# power_supply.net
KiCad netlist of a schematic drawn in Altium Designer
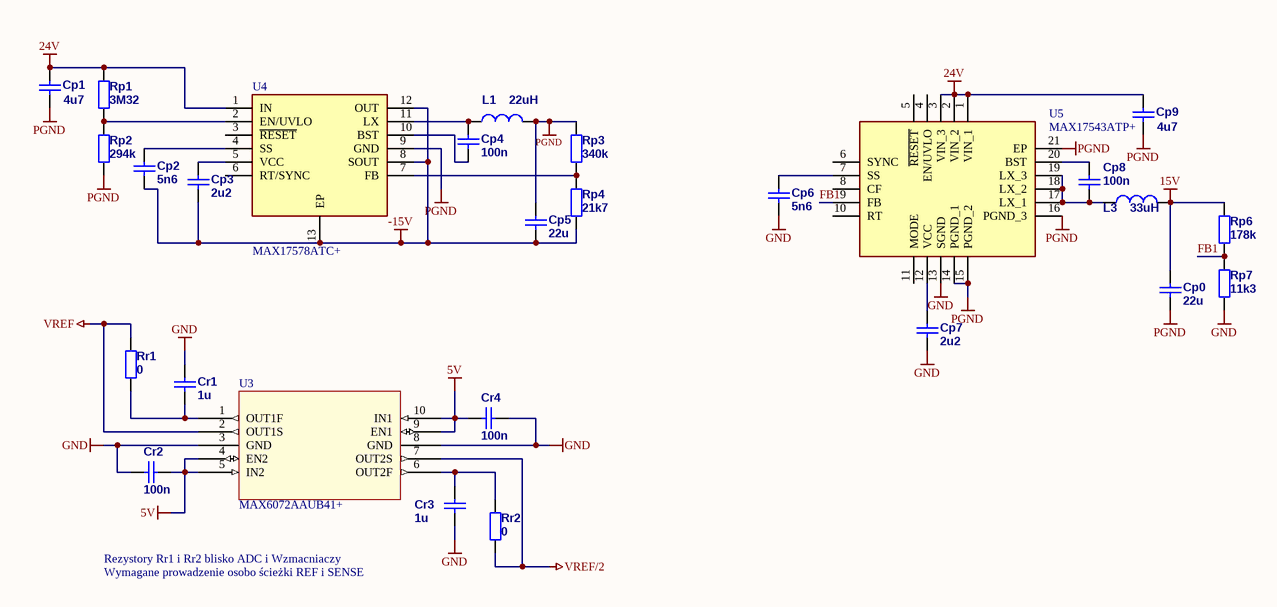
[diagram p0: power_supply.SchDoc]

(export (version "E")
  (design (tool "Eeschema 10.0.6"))
  (components
    (comp (ref "Cp0")
      (value "22u")
      (footprint "C1206")
      (description "Capacitor")
      (libsource (lib "capacitors") (part "Cap"))
    )
    (comp (ref "Cp1")
      (value "4u7")
      (footprint "C1206")
      (description "Capacitor")
      (libsource (lib "capacitors") (part "Cap"))
    )
    (comp (ref "Cp2")
      (value "5n6")
      (footprint "C0603")
      (description "Capacitor")
      (libsource (lib "capacitors") (part "Cap"))
    )
    (comp (ref "Cp3")
      (value "2u2")
      (footprint "C0603")
      (description "Capacitor")
      (libsource (lib "capacitors") (part "Cap"))
    )
    (comp (ref "Cp4")
      (value "100n")
      (footprint "C0603")
      (description "Capacitor")
      (libsource (lib "capacitors") (part "Cap"))
    )
    (comp (ref "Cp5")
      (value "22u")
      (footprint "C1206")
      (description "Capacitor")
      (libsource (lib "capacitors") (part "Cap"))
    )
    (comp (ref "Cp6")
      (value "5n6")
      (footprint "C0603")
      (description "Capacitor")
      (libsource (lib "capacitors") (part "Cap"))
    )
    (comp (ref "Cp7")
      (value "2u2")
      (footprint "C0603")
      (description "Capacitor")
      (libsource (lib "capacitors") (part "Cap"))
    )
    (comp (ref "Cp8")
      (value "100n")
      (footprint "C0603")
      (description "Capacitor")
      (libsource (lib "capacitors") (part "Cap"))
    )
    (comp (ref "Cp9")
      (value "4u7")
      (footprint "C1206")
      (description "Capacitor")
      (libsource (lib "capacitors") (part "Cap"))
    )
    (comp (ref "Cr1")
      (value "1u")
      (footprint "C1206")
      (description "Capacitor")
      (libsource (lib "capacitors") (part "Cap"))
    )
    (comp (ref "Cr2")
      (value "100n")
      (footprint "C0805")
      (description "Capacitor")
      (libsource (lib "capacitors") (part "Cap"))
    )
    (comp (ref "Cr3")
      (value "1u")
      (footprint "C1206")
      (description "Capacitor")
      (libsource (lib "capacitors") (part "Cap"))
    )
    (comp (ref "Cr4")
      (value "100n")
      (footprint "C0805")
      (description "Capacitor")
      (libsource (lib "capacitors") (part "Cap"))
    )
    (comp (ref "L1")
      (value "22uH")
      (footprint "DE1205")
      (description "DE1205-22")
      (libsource (lib "inductors") (part "DE1205-22"))
    )
    (comp (ref "L3")
      (value "33uH")
      (footprint "DE1205")
      (description "DE1205-22")
      (libsource (lib "inductors") (part "DE1205-22"))
    )
    (comp (ref "Rp1")
      (value "3M32")
      (footprint "R0603")
      (description "Resistor")
      (libsource (lib "resistors") (part "Res"))
    )
    (comp (ref "Rp2")
      (value "294k")
      (footprint "R0603")
      (description "Resistor")
      (libsource (lib "resistors") (part "Res"))
    )
    (comp (ref "Rp3")
      (value "340k")
      (footprint "R0603")
      (description "Resistor")
      (libsource (lib "resistors") (part "Res"))
    )
    (comp (ref "Rp4")
      (value "21k7")
      (footprint "R0603")
      (description "Resistor")
      (libsource (lib "resistors") (part "Res"))
    )
    (comp (ref "Rp6")
      (value "178k")
      (footprint "R0603")
      (description "Resistor")
      (libsource (lib "resistors") (part "Res"))
    )
    (comp (ref "Rp7")
      (value "11k3")
      (footprint "R0603")
      (description "Resistor")
      (libsource (lib "resistors") (part "Res"))
    )
    (comp (ref "Rr1")
      (value "0")
      (footprint "R0402")
      (description "Resistor")
      (libsource (lib "resistors") (part "Res"))
    )
    (comp (ref "Rr2")
      (value "0")
      (footprint "R0402")
      (description "Resistor")
      (libsource (lib "resistors") (part "Res"))
    )
    (comp (ref "U3")
      (value "MAX6072AAUB41+")
      (footprint "21-0061L_MXM")
      (description "High-Precision, Dual-Output Series\r\nVoltage Reference")
      (fields
        (field (name "MANUFACTURER_PART_NUMBER") "MAX6072AAUB25+")
        (field (name "COPYRIGHT") "Copyright (C) 2022 Ultra Librarian. All rights reserved.")
      )
      (libsource (lib "RS_IC_vref") (part "MAX6072AAUB41+"))
    )
    (comp (ref "U4")
      (value "MAX17578ATC+")
      (footprint "SamacSys:SON50P300X300X80-13N")
      (description "Integrated Circuit")
      (libsource (lib "*") (part "MAX17578ATC+"))
    )
    (comp (ref "U5")
      (value "MAX17543ATP+")
      (footprint "SamacSys:QFN50P400X400X80-21N")
      (description "Integrated Circuit")
      (libsource (lib "*") (part "MAX17543ATP+"))
    )
  )
  (nets
    (net (code "1") (name "-15V") (class "Default")
      (node (ref "Cp2") (pin "1") (pinfunction "1_1") (pintype "passive"))
      (node (ref "Cp3") (pin "1") (pinfunction "1_1") (pintype "passive"))
      (node (ref "Cp5") (pin "1") (pinfunction "1_1") (pintype "passive"))
      (node (ref "Rp4") (pin "1") (pinfunction "1_1") (pintype "passive"))
      (node (ref "U4") (pin "12") (pinfunction "OUT_12") (pintype "passive"))
      (node (ref "U4") (pin "13") (pinfunction "EP_13") (pintype "passive"))
      (node (ref "U4") (pin "8") (pinfunction "SOUT_8") (pintype "passive"))
    )
    (net (code "2") (name "/FB1") (class "Default")
      (node (ref "Rp6") (pin "1") (pinfunction "1_1") (pintype "passive"))
      (node (ref "Rp7") (pin "2") (pinfunction "2_2") (pintype "passive"))
      (node (ref "U5") (pin "9") (pinfunction "FB_9") (pintype "passive"))
    )
    (net (code "3") (name "5V") (class "Default")
      (node (ref "Cr2") (pin "1") (pinfunction "1_1") (pintype "passive"))
      (node (ref "Cr4") (pin "2") (pinfunction "2_2") (pintype "passive"))
      (node (ref "U3") (pin "10") (pinfunction "IN1_10") (pintype "input"))
      (node (ref "U3") (pin "4") (pinfunction "EN2_4") (pintype "bidirectional"))
      (node (ref "U3") (pin "5") (pinfunction "IN2_5") (pintype "input"))
      (node (ref "U3") (pin "9") (pinfunction "EN1_9") (pintype "bidirectional"))
    )
    (net (code "4") (name "15V") (class "Default")
      (node (ref "Cp0") (pin "2") (pinfunction "2_2") (pintype "passive"))
      (node (ref "L3") (pin "2") (pinfunction "2_2") (pintype "passive"))
      (node (ref "Rp6") (pin "2") (pinfunction "2_2") (pintype "passive"))
    )
    (net (code "5") (name "24V") (class "Default")
      (node (ref "Cp1") (pin "2") (pinfunction "2_2") (pintype "passive"))
      (node (ref "Cp9") (pin "2") (pinfunction "2_2") (pintype "passive"))
      (node (ref "Rp1") (pin "2") (pinfunction "2_2") (pintype "passive"))
      (node (ref "U4") (pin "1") (pinfunction "IN_1") (pintype "passive"))
      (node (ref "U5") (pin "1") (pinfunction "VIN_1_1") (pintype "passive"))
      (node (ref "U5") (pin "2") (pinfunction "VIN_2_2") (pintype "passive"))
      (node (ref "U5") (pin "3") (pinfunction "VIN_3_3") (pintype "passive"))
    )
    (net (code "6") (name "GND") (class "Default")
      (node (ref "Cp6") (pin "1") (pinfunction "1_1") (pintype "passive"))
      (node (ref "Cp7") (pin "1") (pinfunction "1_1") (pintype "passive"))
      (node (ref "Cr1") (pin "2") (pinfunction "2_2") (pintype "passive"))
      (node (ref "Cr2") (pin "2") (pinfunction "2_2") (pintype "passive"))
      (node (ref "Cr3") (pin "1") (pinfunction "1_1") (pintype "passive"))
      (node (ref "Cr4") (pin "1") (pinfunction "1_1") (pintype "passive"))
      (node (ref "Rp7") (pin "1") (pinfunction "1_1") (pintype "passive"))
      (node (ref "U3") (pin "3") (pinfunction "GND_3") (pintype "passive"))
      (node (ref "U3") (pin "8") (pinfunction "GND_8") (pintype "passive"))
      (node (ref "U5") (pin "13") (pinfunction "SGND_13") (pintype "passive"))
    )
    (net (code "7") (name "Net-(U3-OUT1F)") (class "Default")
      (node (ref "Cr1") (pin "1") (pinfunction "1_1") (pintype "passive"))
      (node (ref "Rr1") (pin "1") (pinfunction "1_1") (pintype "passive"))
      (node (ref "U3") (pin "1") (pinfunction "OUT1F_1") (pintype "output"))
    )
    (net (code "8") (name "Net-(U3-OUT2F)") (class "Default")
      (node (ref "Cr3") (pin "2") (pinfunction "2_2") (pintype "passive"))
      (node (ref "Rr2") (pin "2") (pinfunction "2_2") (pintype "passive"))
      (node (ref "U3") (pin "6") (pinfunction "OUT2F_6") (pintype "output"))
    )
    (net (code "9") (name "Net-(U4-BST)") (class "Default")
      (node (ref "Cp4") (pin "2") (pinfunction "2_2") (pintype "passive"))
      (node (ref "U4") (pin "10") (pinfunction "BST_10") (pintype "passive"))
    )
    (net (code "10") (name "Net-(U4-EN{slash}UVLO)") (class "Default")
      (node (ref "Rp1") (pin "1") (pinfunction "1_1") (pintype "passive"))
      (node (ref "Rp2") (pin "2") (pinfunction "2_2") (pintype "passive"))
      (node (ref "U4") (pin "2") (pinfunction "EN/UVLO_2") (pintype "passive"))
    )
    (net (code "11") (name "Net-(U4-FB)") (class "Default")
      (node (ref "Rp3") (pin "1") (pinfunction "1_1") (pintype "passive"))
      (node (ref "Rp4") (pin "2") (pinfunction "2_2") (pintype "passive"))
      (node (ref "U4") (pin "7") (pinfunction "FB_7") (pintype "passive"))
    )
    (net (code "12") (name "Net-(U4-LX)") (class "Default")
      (node (ref "Cp4") (pin "1") (pinfunction "1_1") (pintype "passive"))
      (node (ref "L1") (pin "1") (pinfunction "1_1") (pintype "passive"))
      (node (ref "U4") (pin "11") (pinfunction "LX_11") (pintype "passive"))
    )
    (net (code "13") (name "Net-(U4-SS)") (class "Default")
      (node (ref "Cp2") (pin "2") (pinfunction "2_2") (pintype "passive"))
      (node (ref "U4") (pin "4") (pinfunction "SS_4") (pintype "passive"))
    )
    (net (code "14") (name "Net-(U4-VCC)") (class "Default")
      (node (ref "Cp3") (pin "2") (pinfunction "2_2") (pintype "passive"))
      (node (ref "U4") (pin "5") (pinfunction "VCC_5") (pintype "passive"))
    )
    (net (code "15") (name "Net-(U5-BST)") (class "Default")
      (node (ref "Cp8") (pin "2") (pinfunction "2_2") (pintype "passive"))
      (node (ref "U5") (pin "20") (pinfunction "BST_20") (pintype "passive"))
    )
    (net (code "16") (name "Net-(U5-LX_1)") (class "Default")
      (node (ref "Cp8") (pin "1") (pinfunction "1_1") (pintype "passive"))
      (node (ref "L3") (pin "1") (pinfunction "1_1") (pintype "passive"))
      (node (ref "U5") (pin "17") (pinfunction "LX_1_17") (pintype "passive"))
      (node (ref "U5") (pin "18") (pinfunction "LX_2_18") (pintype "passive"))
      (node (ref "U5") (pin "19") (pinfunction "LX_3_19") (pintype "passive"))
    )
    (net (code "17") (name "Net-(U5-SS)") (class "Default")
      (node (ref "Cp6") (pin "2") (pinfunction "2_2") (pintype "passive"))
      (node (ref "U5") (pin "7") (pinfunction "SS_7") (pintype "passive"))
    )
    (net (code "18") (name "Net-(U5-VCC)") (class "Default")
      (node (ref "Cp7") (pin "2") (pinfunction "2_2") (pintype "passive"))
      (node (ref "U5") (pin "12") (pinfunction "VCC_12") (pintype "passive"))
    )
    (net (code "19") (name "PGND") (class "Default")
      (node (ref "Cp0") (pin "1") (pinfunction "1_1") (pintype "passive"))
      (node (ref "Cp1") (pin "1") (pinfunction "1_1") (pintype "passive"))
      (node (ref "Cp5") (pin "2") (pinfunction "2_2") (pintype "passive"))
      (node (ref "Cp9") (pin "1") (pinfunction "1_1") (pintype "passive"))
      (node (ref "L1") (pin "2") (pinfunction "2_2") (pintype "passive"))
      (node (ref "Rp2") (pin "1") (pinfunction "1_1") (pintype "passive"))
      (node (ref "Rp3") (pin "2") (pinfunction "2_2") (pintype "passive"))
      (node (ref "U4") (pin "9") (pinfunction "GND_9") (pintype "passive"))
      (node (ref "U5") (pin "14") (pinfunction "PGND_1_14") (pintype "passive"))
      (node (ref "U5") (pin "15") (pinfunction "PGND_2_15") (pintype "passive"))
      (node (ref "U5") (pin "16") (pinfunction "PGND_3_16") (pintype "passive"))
      (node (ref "U5") (pin "21") (pinfunction "EP_21") (pintype "passive"))
    )
    (net (code "20") (name "VREF") (class "Default")
      (node (ref "Rr1") (pin "2") (pinfunction "2_2") (pintype "passive"))
      (node (ref "U3") (pin "2") (pinfunction "OUT1S_2") (pintype "output"))
    )
    (net (code "21") (name "VREF{slash}2") (class "Default")
      (node (ref "Rr2") (pin "1") (pinfunction "1_1") (pintype "passive"))
      (node (ref "U3") (pin "7") (pinfunction "OUT2S_7") (pintype "output"))
    )
    (net (code "22") (name "unconnected-(U4-RT{slash}SYNC-Pad6)") (class "Default")
      (node (ref "U4") (pin "6") (pinfunction "RT/SYNC_6") (pintype "passive"))
    )
    (net (code "23") (name "unconnected-(U4-~{RESET}-Pad3)") (class "Default")
      (node (ref "U4") (pin "3") (pinfunction "~{RESET}_3") (pintype "passive"))
    )
    (net (code "24") (name "unconnected-(U5-CF-Pad8)") (class "Default")
      (node (ref "U5") (pin "8") (pinfunction "CF_8") (pintype "passive"))
    )
    (net (code "25") (name "unconnected-(U5-EN{slash}UVLO-Pad4)") (class "Default")
      (node (ref "U5") (pin "4") (pinfunction "EN/UVLO_4") (pintype "passive"))
    )
    (net (code "26") (name "unconnected-(U5-MODE-Pad11)") (class "Default")
      (node (ref "U5") (pin "11") (pinfunction "MODE_11") (pintype "passive"))
    )
    (net (code "27") (name "unconnected-(U5-RT-Pad10)") (class "Default")
      (node (ref "U5") (pin "10") (pinfunction "RT_10") (pintype "passive"))
    )
    (net (code "28") (name "unconnected-(U5-SYNC-Pad6)") (class "Default")
      (node (ref "U5") (pin "6") (pinfunction "SYNC_6") (pintype "passive"))
    )
    (net (code "29") (name "unconnected-(U5-~{RESET}-Pad5)") (class "Default")
      (node (ref "U5") (pin "5") (pinfunction "~{RESET}_5") (pintype "passive"))
    )
  )
)
